# Fire_Warning.net
KiCad netlist of a schematic drawn in Altium Designer
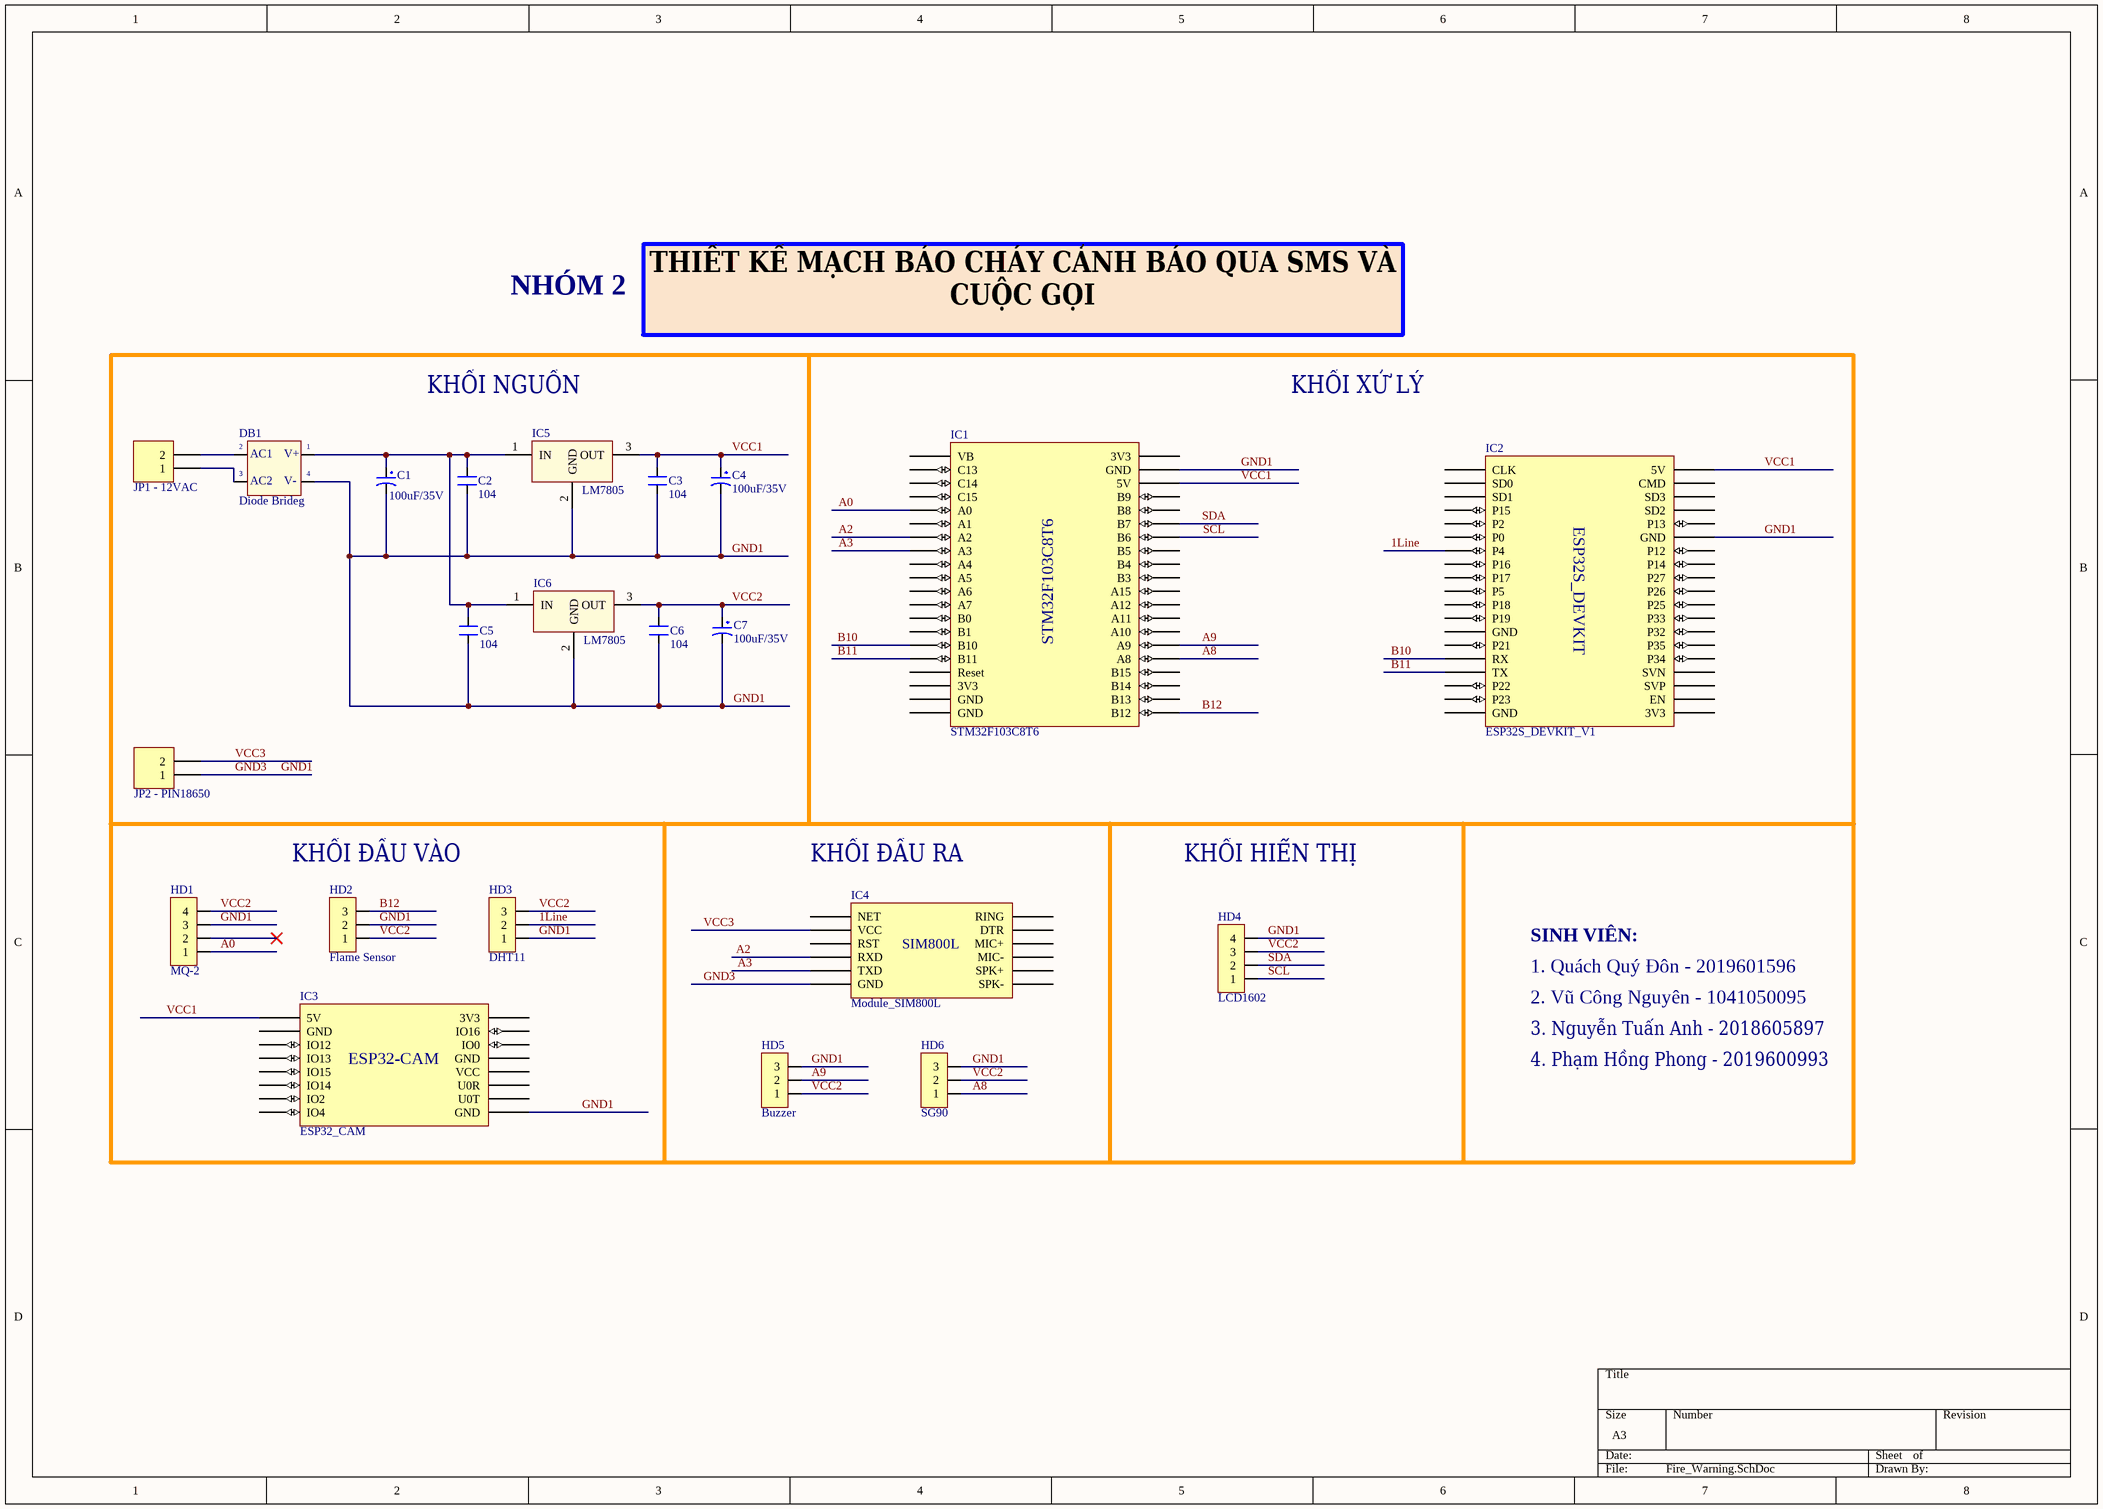
[diagram p0: Fire_Warning.SchDoc]

(export (version "E")
  (design (tool "Eeschema 10.0.6"))
  (components
    (comp (ref "C1")
      (value "100uF/35V")
      (footprint "CP1.5/3.4")
      (description "Cap 100uF/35V - 470uF/16V")
      (libsource (lib "library2") (part "CP3"))
    )
    (comp (ref "C2")
      (value "104")
      (footprint "CN2")
      (description "Cap np 104 => 105pF")
      (libsource (lib "Thuvien3D") (part "CN2"))
    )
    (comp (ref "C3")
      (value "104")
      (footprint "CN2")
      (description "Cap np 104 => 105pF")
      (libsource (lib "Thuvien3D") (part "CN2"))
    )
    (comp (ref "C4")
      (value "100uF/35V")
      (footprint "CP1.5/3.4")
      (description "Cap 100uF/35V - 470uF/16V")
      (libsource (lib "library2") (part "CP3"))
    )
    (comp (ref "C5")
      (value "104")
      (footprint "CN2")
      (description "Cap np 104 => 105pF")
      (libsource (lib "Thuvien3D") (part "CN2"))
    )
    (comp (ref "C6")
      (value "104")
      (footprint "CN2")
      (description "Cap np 104 => 105pF")
      (libsource (lib "Thuvien3D") (part "CN2"))
    )
    (comp (ref "C7")
      (value "100uF/35V")
      (footprint "CP1.5/3.4")
      (description "Cap 100uF/35V - 470uF/16V")
      (libsource (lib "library2") (part "CP3"))
    )
    (comp (ref "DB1")
      (value "Diode Brideg")
      (footprint "CAU 5A")
      (description "Convert AC to DC voltage, 4 pin")
      (libsource (lib "Thuvien3D") (part "DB"))
    )
    (comp (ref "HD1")
      (value "MQ-2")
      (footprint "HEADER 4")
      (description "Header 4P XH2.54 thẳng")
      (libsource (lib "library1") (part "Header 4_MH"))
    )
    (comp (ref "HD2")
      (value "Flame Sensor")
      (footprint "HEADER 3")
      (description "Header 3P XH2.54 thẳng")
      (libsource (lib "library1") (part "Header 3_MH"))
    )
    (comp (ref "HD3")
      (value "DHT11")
      (footprint "HEADER 3")
      (description "Header 3P XH2.54 thẳng")
      (libsource (lib "library1") (part "Header 3_MH"))
    )
    (comp (ref "HD4")
      (value "LCD1602")
      (footprint "HEADER 4")
      (description "Header 4P XH2.54 thẳng")
      (libsource (lib "library1") (part "Header 4_MH"))
    )
    (comp (ref "HD5")
      (value "Buzzer")
      (footprint "HEADER 3")
      (description "Header 3P XH2.54 thẳng")
      (libsource (lib "library1") (part "Header 3_MH"))
    )
    (comp (ref "HD6")
      (value "SG90")
      (footprint "HEADER 3")
      (description "Header 3P XH2.54 thẳng")
      (libsource (lib "library1") (part "Header 3_MH"))
    )
    (comp (ref "IC1")
      (value "STM32F103C8T6")
      (footprint "STM32F103C8T6")
      (libsource (lib "MCU") (part "STM32F103C8T6"))
    )
    (comp (ref "IC2")
      (value "ESP32S_DEVKIT_V1")
      (footprint "ESP32S_DEVKIT_V1")
      (libsource (lib "MCU") (part "ESP32S_DEVKIT_V1"))
    )
    (comp (ref "IC3") (value "ESP32_CAM") (footprint "ESP32_CAM") (libsource (lib "MCU") (part "ESP32_CAM")))
    (comp (ref "IC4")
      (value "Module_SIM800L")
      (footprint "Module Sim800L")
      (libsource (lib "MCU") (part "Module_SIM800L"))
    )
    (comp (ref "IC5")
      (value "LM7805")
      (footprint "QTO-220")
      (description "On ap +, from + 5 to + 24VDC")
      (libsource (lib "Thuvien3D") (part "LM78xx"))
    )
    (comp (ref "IC6")
      (value "LM7805")
      (footprint "QTO-220")
      (description "On ap +, from + 5 to + 24VDC")
      (libsource (lib "Thuvien3D") (part "LM78xx"))
    )
    (comp (ref "JP1 - 12VAC")
      (value "Header 2_1")
      (footprint "HED2")
      (description "Header, 2-Pin")
      (fields (field (name "MANUFACTURER") "Generic Components"))
      (libsource (lib "Thuvien3D") (part "Header 2_1"))
    )
    (comp (ref "JP2 - PIN18650")
      (value "Header 2_1")
      (footprint "HED2")
      (description "Header, 2-Pin")
      (fields (field (name "MANUFACTURER") "Generic Components"))
      (libsource (lib "Thuvien3D") (part "Header 2_1"))
    )
  )
  (nets
    (net (code "1") (name "/1Line") (class "Default")
      (node (ref "HD3") (pin "2") (pinfunction "2_2") (pintype "passive"))
      (node (ref "IC2") (pin "7") (pinfunction "P4_7") (pintype "bidirectional"))
    )
    (net (code "2") (name "/A0") (class "Default")
      (node (ref "HD1") (pin "1") (pinfunction "1_1") (pintype "passive"))
      (node (ref "IC1") (pin "24") (pinfunction "A0_24") (pintype "bidirectional"))
    )
    (net (code "3") (name "/A2") (class "Default")
      (node (ref "IC1") (pin "26") (pinfunction "A2_26") (pintype "bidirectional"))
      (node (ref "IC4") (pin "4") (pinfunction "RXD_4") (pintype "passive"))
    )
    (net (code "4") (name "/A3") (class "Default")
      (node (ref "IC1") (pin "27") (pinfunction "A3_27") (pintype "bidirectional"))
      (node (ref "IC4") (pin "5") (pinfunction "TXD_5") (pintype "passive"))
    )
    (net (code "5") (name "/A8") (class "Default")
      (node (ref "HD6") (pin "1") (pinfunction "1_1") (pintype "passive"))
      (node (ref "IC1") (pin "4") (pinfunction "A8_4") (pintype "bidirectional"))
    )
    (net (code "6") (name "/A9") (class "Default")
      (node (ref "HD5") (pin "2") (pinfunction "2_2") (pintype "passive"))
      (node (ref "IC1") (pin "5") (pinfunction "A9_5") (pintype "bidirectional"))
    )
    (net (code "7") (name "/B10") (class "Default")
      (node (ref "IC1") (pin "34") (pinfunction "B10_34") (pintype "bidirectional"))
      (node (ref "IC2") (pin "15") (pinfunction "RX_15") (pintype "passive"))
    )
    (net (code "8") (name "/B11") (class "Default")
      (node (ref "IC1") (pin "35") (pinfunction "B11_35") (pintype "bidirectional"))
      (node (ref "IC2") (pin "16") (pinfunction "TX_16") (pintype "passive"))
    )
    (net (code "9") (name "/B12") (class "Default")
      (node (ref "HD2") (pin "3") (pinfunction "3_3") (pintype "passive"))
      (node (ref "IC1") (pin "0") (pinfunction "B12_0") (pintype "bidirectional"))
    )
    (net (code "10") (name "/GND1") (class "Default")
      (node (ref "C1") (pin "2") (pinfunction "2_2") (pintype "passive"))
      (node (ref "C2") (pin "1") (pinfunction "1_1") (pintype "passive"))
      (node (ref "C3") (pin "1") (pinfunction "1_1") (pintype "passive"))
      (node (ref "C4") (pin "2") (pinfunction "2_2") (pintype "passive"))
      (node (ref "C5") (pin "1") (pinfunction "1_1") (pintype "passive"))
      (node (ref "C6") (pin "1") (pinfunction "1_1") (pintype "passive"))
      (node (ref "C7") (pin "2") (pinfunction "2_2") (pintype "passive"))
      (node (ref "DB1") (pin "4") (pinfunction "-V_OUT_4") (pintype "passive"))
      (node (ref "HD1") (pin "3") (pinfunction "3_3") (pintype "passive"))
      (node (ref "HD2") (pin "2") (pinfunction "2_2") (pintype "passive"))
      (node (ref "HD3") (pin "1") (pinfunction "1_1") (pintype "passive"))
      (node (ref "HD4") (pin "4") (pinfunction "4_4") (pintype "passive"))
      (node (ref "HD5") (pin "3") (pinfunction "3_3") (pintype "passive"))
      (node (ref "HD6") (pin "3") (pinfunction "3_3") (pintype "passive"))
      (node (ref "IC1") (pin "18") (pinfunction "GND_18") (pintype "power_in"))
      (node (ref "IC2") (pin "33") (pinfunction "GND_33") (pintype "power_in"))
      (node (ref "IC3") (pin "1") (pinfunction "GND_1") (pintype "power_in"))
      (node (ref "IC4") (pin "6") (pinfunction "GND_6") (pintype "power_in"))
      (node (ref "IC5") (pin "2") (pinfunction "GND_2") (pintype "passive"))
      (node (ref "IC6") (pin "2") (pinfunction "GND_2") (pintype "passive"))
      (node (ref "JP2 - PIN18650") (pin "1") (pinfunction "1_1") (pintype "passive"))
    )
    (net (code "11") (name "/SCL") (class "Default")
      (node (ref "HD4") (pin "1") (pinfunction "1_1") (pintype "passive"))
      (node (ref "IC1") (pin "13") (pinfunction "B6_13") (pintype "bidirectional"))
    )
    (net (code "12") (name "/SDA") (class "Default")
      (node (ref "HD4") (pin "2") (pinfunction "2_2") (pintype "passive"))
      (node (ref "IC1") (pin "14") (pinfunction "B7_14") (pintype "bidirectional"))
    )
    (net (code "13") (name "/VCC1") (class "Default")
      (node (ref "C3") (pin "2") (pinfunction "2_2") (pintype "passive"))
      (node (ref "C4") (pin "1") (pinfunction "1_1") (pintype "passive"))
      (node (ref "IC1") (pin "17") (pinfunction "5V_17") (pintype "power_in"))
      (node (ref "IC2") (pin "38") (pinfunction "5V_38") (pintype "power_in"))
      (node (ref "IC3") (pin "9") (pinfunction "5V_9") (pintype "power_in"))
      (node (ref "IC5") (pin "3") (pinfunction "OUT_3") (pintype "passive"))
    )
    (net (code "14") (name "/VCC2") (class "Default")
      (node (ref "C6") (pin "2") (pinfunction "2_2") (pintype "passive"))
      (node (ref "C7") (pin "1") (pinfunction "1_1") (pintype "passive"))
      (node (ref "HD1") (pin "4") (pinfunction "4_4") (pintype "passive"))
      (node (ref "HD2") (pin "1") (pinfunction "1_1") (pintype "passive"))
      (node (ref "HD3") (pin "3") (pinfunction "3_3") (pintype "passive"))
      (node (ref "HD4") (pin "3") (pinfunction "3_3") (pintype "passive"))
      (node (ref "HD5") (pin "1") (pinfunction "1_1") (pintype "passive"))
      (node (ref "HD6") (pin "2") (pinfunction "2_2") (pintype "passive"))
      (node (ref "IC6") (pin "3") (pinfunction "OUT_3") (pintype "passive"))
    )
    (net (code "15") (name "/VCC3") (class "Default")
      (node (ref "IC4") (pin "2") (pinfunction "VCC_2") (pintype "power_in"))
      (node (ref "JP2 - PIN18650") (pin "2") (pinfunction "2_2") (pintype "passive"))
    )
    (net (code "16") (name "Net-(DB1-+V_OUT)") (class "Default")
      (node (ref "C1") (pin "1") (pinfunction "1_1") (pintype "passive"))
      (node (ref "C2") (pin "2") (pinfunction "2_2") (pintype "passive"))
      (node (ref "C5") (pin "2") (pinfunction "2_2") (pintype "passive"))
      (node (ref "DB1") (pin "1") (pinfunction "+V_OUT_1") (pintype "passive"))
      (node (ref "IC5") (pin "1") (pinfunction "IN_1") (pintype "passive"))
      (node (ref "IC6") (pin "1") (pinfunction "IN_1") (pintype "passive"))
    )
    (net (code "17") (name "Net-(DB1-AC1)") (class "Default")
      (node (ref "DB1") (pin "2") (pinfunction "AC1_2") (pintype "passive"))
      (node (ref "JP1 - 12VAC") (pin "2") (pinfunction "2_2") (pintype "passive"))
    )
    (net (code "18") (name "Net-(DB1-AC2)") (class "Default")
      (node (ref "DB1") (pin "3") (pinfunction "AC2_3") (pintype "passive"))
      (node (ref "JP1 - 12VAC") (pin "1") (pinfunction "1_1") (pintype "passive"))
    )
    (net (code "19") (name "unconnected-(HD1-Pad2)") (class "Default")
      (node (ref "HD1") (pin "2") (pinfunction "2_2") (pintype "passive+no_connect"))
    )
    (net (code "20") (name "unconnected-(IC1-3V3-Pad19)") (class "Default")
      (node (ref "IC1") (pin "19") (pinfunction "3V3_19") (pintype "power_in"))
    )
    (net (code "21") (name "unconnected-(IC1-3V3-Pad37)") (class "Default")
      (node (ref "IC1") (pin "37") (pinfunction "3V3_37") (pintype "power_in"))
    )
    (net (code "22") (name "unconnected-(IC1-A1-Pad25)") (class "Default")
      (node (ref "IC1") (pin "25") (pinfunction "A1_25") (pintype "bidirectional"))
    )
    (net (code "23") (name "unconnected-(IC1-A4-Pad28)") (class "Default")
      (node (ref "IC1") (pin "28") (pinfunction "A4_28") (pintype "bidirectional"))
    )
    (net (code "24") (name "unconnected-(IC1-A5-Pad29)") (class "Default")
      (node (ref "IC1") (pin "29") (pinfunction "A5_29") (pintype "bidirectional"))
    )
    (net (code "25") (name "unconnected-(IC1-A6-Pad30)") (class "Default")
      (node (ref "IC1") (pin "30") (pinfunction "A6_30") (pintype "bidirectional"))
    )
    (net (code "26") (name "unconnected-(IC1-A7-Pad31)") (class "Default")
      (node (ref "IC1") (pin "31") (pinfunction "A7_31") (pintype "bidirectional"))
    )
    (net (code "27") (name "unconnected-(IC1-A10-Pad6)") (class "Default")
      (node (ref "IC1") (pin "6") (pinfunction "A10_6") (pintype "bidirectional"))
    )
    (net (code "28") (name "unconnected-(IC1-A11-Pad7)") (class "Default")
      (node (ref "IC1") (pin "7") (pinfunction "A11_7") (pintype "bidirectional"))
    )
    (net (code "29") (name "unconnected-(IC1-A12-Pad8)") (class "Default")
      (node (ref "IC1") (pin "8") (pinfunction "A12_8") (pintype "bidirectional"))
    )
    (net (code "30") (name "unconnected-(IC1-A15-Pad9)") (class "Default")
      (node (ref "IC1") (pin "9") (pinfunction "A15_9") (pintype "bidirectional"))
    )
    (net (code "31") (name "unconnected-(IC1-B0-Pad32)") (class "Default")
      (node (ref "IC1") (pin "32") (pinfunction "B0_32") (pintype "bidirectional"))
    )
    (net (code "32") (name "unconnected-(IC1-B1-Pad33)") (class "Default")
      (node (ref "IC1") (pin "33") (pinfunction "B1_33") (pintype "bidirectional"))
    )
    (net (code "33") (name "unconnected-(IC1-B3-Pad10)") (class "Default")
      (node (ref "IC1") (pin "10") (pinfunction "B3_10") (pintype "bidirectional"))
    )
    (net (code "34") (name "unconnected-(IC1-B4-Pad11)") (class "Default")
      (node (ref "IC1") (pin "11") (pinfunction "B4_11") (pintype "bidirectional"))
    )
    (net (code "35") (name "unconnected-(IC1-B5-Pad12)") (class "Default")
      (node (ref "IC1") (pin "12") (pinfunction "B5_12") (pintype "bidirectional"))
    )
    (net (code "36") (name "unconnected-(IC1-B8-Pad15)") (class "Default")
      (node (ref "IC1") (pin "15") (pinfunction "B8_15") (pintype "bidirectional"))
    )
    (net (code "37") (name "unconnected-(IC1-B9-Pad16)") (class "Default")
      (node (ref "IC1") (pin "16") (pinfunction "B9_16") (pintype "bidirectional"))
    )
    (net (code "38") (name "unconnected-(IC1-B13-Pad1)") (class "Default")
      (node (ref "IC1") (pin "1") (pinfunction "B13_1") (pintype "bidirectional"))
    )
    (net (code "39") (name "unconnected-(IC1-B14-Pad2)") (class "Default")
      (node (ref "IC1") (pin "2") (pinfunction "B14_2") (pintype "bidirectional"))
    )
    (net (code "40") (name "unconnected-(IC1-B15-Pad3)") (class "Default")
      (node (ref "IC1") (pin "3") (pinfunction "B15_3") (pintype "bidirectional"))
    )
    (net (code "41") (name "unconnected-(IC1-C13-Pad21)") (class "Default")
      (node (ref "IC1") (pin "21") (pinfunction "C13_21") (pintype "bidirectional"))
    )
    (net (code "42") (name "unconnected-(IC1-C14-Pad22)") (class "Default")
      (node (ref "IC1") (pin "22") (pinfunction "C14_22") (pintype "bidirectional"))
    )
    (net (code "43") (name "unconnected-(IC1-C15-Pad23)") (class "Default")
      (node (ref "IC1") (pin "23") (pinfunction "C15_23") (pintype "bidirectional"))
    )
    (net (code "44") (name "unconnected-(IC1-GND-Pad38)") (class "Default")
      (node (ref "IC1") (pin "38") (pinfunction "GND_38") (pintype "power_in"))
    )
    (net (code "45") (name "unconnected-(IC1-GND-Pad39)") (class "Default")
      (node (ref "IC1") (pin "39") (pinfunction "GND_39") (pintype "power_in"))
    )
    (net (code "46") (name "unconnected-(IC1-Reset-Pad36)") (class "Default")
      (node (ref "IC1") (pin "36") (pinfunction "Reset_36") (pintype "passive"))
    )
    (net (code "47") (name "unconnected-(IC1-VB-Pad20)") (class "Default")
      (node (ref "IC1") (pin "20") (pinfunction "VB_20") (pintype "passive"))
    )
    (net (code "48") (name "unconnected-(IC2-3V3-Pad20)") (class "Default")
      (node (ref "IC2") (pin "20") (pinfunction "3V3_20") (pintype "passive"))
    )
    (net (code "49") (name "unconnected-(IC2-CLK-Pad1)") (class "Default")
      (node (ref "IC2") (pin "1") (pinfunction "CLK_1") (pintype "passive"))
    )
    (net (code "50") (name "unconnected-(IC2-CMD-Pad37)") (class "Default")
      (node (ref "IC2") (pin "37") (pinfunction "CMD_37") (pintype "passive"))
    )
    (net (code "51") (name "unconnected-(IC2-EN-Pad21)") (class "Default")
      (node (ref "IC2") (pin "21") (pinfunction "EN_21") (pintype "passive"))
    )
    (net (code "52") (name "unconnected-(IC2-GND-Pad13)") (class "Default")
      (node (ref "IC2") (pin "13") (pinfunction "GND_13") (pintype "power_in"))
    )
    (net (code "53") (name "unconnected-(IC2-GND-Pad19)") (class "Default")
      (node (ref "IC2") (pin "19") (pinfunction "GND_19") (pintype "power_in"))
    )
    (net (code "54") (name "unconnected-(IC2-P0-Pad6)") (class "Default")
      (node (ref "IC2") (pin "6") (pinfunction "P0_6") (pintype "bidirectional"))
    )
    (net (code "55") (name "unconnected-(IC2-P2-Pad5)") (class "Default")
      (node (ref "IC2") (pin "5") (pinfunction "P2_5") (pintype "bidirectional"))
    )
    (net (code "56") (name "unconnected-(IC2-P5-Pad10)") (class "Default")
      (node (ref "IC2") (pin "10") (pinfunction "P5_10") (pintype "bidirectional"))
    )
    (net (code "57") (name "unconnected-(IC2-P12-Pad32)") (class "Default")
      (node (ref "IC2") (pin "32") (pinfunction "P12_32") (pintype "bidirectional"))
    )
    (net (code "58") (name "unconnected-(IC2-P13-Pad34)") (class "Default")
      (node (ref "IC2") (pin "34") (pinfunction "P13_34") (pintype "bidirectional"))
    )
    (net (code "59") (name "unconnected-(IC2-P14-Pad31)") (class "Default")
      (node (ref "IC2") (pin "31") (pinfunction "P14_31") (pintype "bidirectional"))
    )
    (net (code "60") (name "unconnected-(IC2-P15-Pad4)") (class "Default")
      (node (ref "IC2") (pin "4") (pinfunction "P15_4") (pintype "bidirectional"))
    )
    (net (code "61") (name "unconnected-(IC2-P16-Pad8)") (class "Default")
      (node (ref "IC2") (pin "8") (pinfunction "P16_8") (pintype "bidirectional"))
    )
    (net (code "62") (name "unconnected-(IC2-P17-Pad9)") (class "Default")
      (node (ref "IC2") (pin "9") (pinfunction "P17_9") (pintype "bidirectional"))
    )
    (net (code "63") (name "unconnected-(IC2-P18-Pad11)") (class "Default")
      (node (ref "IC2") (pin "11") (pinfunction "P18_11") (pintype "bidirectional"))
    )
    (net (code "64") (name "unconnected-(IC2-P19-Pad12)") (class "Default")
      (node (ref "IC2") (pin "12") (pinfunction "P19_12") (pintype "bidirectional"))
    )
    (net (code "65") (name "unconnected-(IC2-P21-Pad14)") (class "Default")
      (node (ref "IC2") (pin "14") (pinfunction "P21_14") (pintype "bidirectional"))
    )
    (net (code "66") (name "unconnected-(IC2-P22-Pad17)") (class "Default")
      (node (ref "IC2") (pin "17") (pinfunction "P22_17") (pintype "bidirectional"))
    )
    (net (code "67") (name "unconnected-(IC2-P23-Pad18)") (class "Default")
      (node (ref "IC2") (pin "18") (pinfunction "P23_18") (pintype "bidirectional"))
    )
    (net (code "68") (name "unconnected-(IC2-P25-Pad28)") (class "Default")
      (node (ref "IC2") (pin "28") (pinfunction "P25_28") (pintype "bidirectional"))
    )
    (net (code "69") (name "unconnected-(IC2-P26-Pad29)") (class "Default")
      (node (ref "IC2") (pin "29") (pinfunction "P26_29") (pintype "bidirectional"))
    )
    (net (code "70") (name "unconnected-(IC2-P27-Pad30)") (class "Default")
      (node (ref "IC2") (pin "30") (pinfunction "P27_30") (pintype "bidirectional"))
    )
    (net (code "71") (name "unconnected-(IC2-P32-Pad26)") (class "Default")
      (node (ref "IC2") (pin "26") (pinfunction "P32_26") (pintype "bidirectional"))
    )
    (net (code "72") (name "unconnected-(IC2-P33-Pad27)") (class "Default")
      (node (ref "IC2") (pin "27") (pinfunction "P33_27") (pintype "bidirectional"))
    )
    (net (code "73") (name "unconnected-(IC2-P34-Pad24)") (class "Default")
      (node (ref "IC2") (pin "24") (pinfunction "P34_24") (pintype "bidirectional"))
    )
    (net (code "74") (name "unconnected-(IC2-P35-Pad25)") (class "Default")
      (node (ref "IC2") (pin "25") (pinfunction "P35_25") (pintype "bidirectional"))
    )
    (net (code "75") (name "unconnected-(IC2-SD0-Pad2)") (class "Default")
      (node (ref "IC2") (pin "2") (pinfunction "SD0_2") (pintype "passive"))
    )
    (net (code "76") (name "unconnected-(IC2-SD1-Pad3)") (class "Default")
      (node (ref "IC2") (pin "3") (pinfunction "SD1_3") (pintype "passive"))
    )
    (net (code "77") (name "unconnected-(IC2-SD2-Pad35)") (class "Default")
      (node (ref "IC2") (pin "35") (pinfunction "SD2_35") (pintype "passive"))
    )
    (net (code "78") (name "unconnected-(IC2-SD3-Pad36)") (class "Default")
      (node (ref "IC2") (pin "36") (pinfunction "SD3_36") (pintype "passive"))
    )
    (net (code "79") (name "unconnected-(IC2-SVN-Pad23)") (class "Default")
      (node (ref "IC2") (pin "23") (pinfunction "SVN_23") (pintype "passive"))
    )
    (net (code "80") (name "unconnected-(IC2-SVP-Pad22)") (class "Default")
      (node (ref "IC2") (pin "22") (pinfunction "SVP_22") (pintype "passive"))
    )
    (net (code "81") (name "unconnected-(IC3-3V3-Pad8)") (class "Default")
      (node (ref "IC3") (pin "8") (pinfunction "3V3_8") (pintype "power_in"))
    )
    (net (code "82") (name "unconnected-(IC3-GND-Pad5)") (class "Default")
      (node (ref "IC3") (pin "5") (pinfunction "GND_5") (pintype "power_in"))
    )
    (net (code "83") (name "unconnected-(IC3-GND-Pad10)") (class "Default")
      (node (ref "IC3") (pin "10") (pinfunction "GND_10") (pintype "power_in"))
    )
    (net (code "84") (name "unconnected-(IC3-IO0-Pad6)") (class "Default")
      (node (ref "IC3") (pin "6") (pinfunction "IO0_6") (pintype "bidirectional"))
    )
    (net (code "85") (name "unconnected-(IC3-IO2-Pad15)") (class "Default")
      (node (ref "IC3") (pin "15") (pinfunction "IO2_15") (pintype "bidirectional"))
    )
    (net (code "86") (name "unconnected-(IC3-IO4-Pad16)") (class "Default")
      (node (ref "IC3") (pin "16") (pinfunction "IO4_16") (pintype "bidirectional"))
    )
    (net (code "87") (name "unconnected-(IC3-IO12-Pad11)") (class "Default")
      (node (ref "IC3") (pin "11") (pinfunction "IO12_11") (pintype "bidirectional"))
    )
    (net (code "88") (name "unconnected-(IC3-IO13-Pad12)") (class "Default")
      (node (ref "IC3") (pin "12") (pinfunction "IO13_12") (pintype "bidirectional"))
    )
    (net (code "89") (name "unconnected-(IC3-IO14-Pad14)") (class "Default")
      (node (ref "IC3") (pin "14") (pinfunction "IO14_14") (pintype "bidirectional"))
    )
    (net (code "90") (name "unconnected-(IC3-IO15-Pad13)") (class "Default")
      (node (ref "IC3") (pin "13") (pinfunction "IO15_13") (pintype "bidirectional"))
    )
    (net (code "91") (name "unconnected-(IC3-IO16-Pad7)") (class "Default")
      (node (ref "IC3") (pin "7") (pinfunction "IO16_7") (pintype "bidirectional"))
    )
    (net (code "92") (name "unconnected-(IC3-U0R-Pad3)") (class "Default")
      (node (ref "IC3") (pin "3") (pinfunction "U0R_3") (pintype "passive"))
    )
    (net (code "93") (name "unconnected-(IC3-U0T-Pad2)") (class "Default")
      (node (ref "IC3") (pin "2") (pinfunction "U0T_2") (pintype "passive"))
    )
    (net (code "94") (name "unconnected-(IC3-VCC-Pad4)") (class "Default")
      (node (ref "IC3") (pin "4") (pinfunction "VCC_4") (pintype "power_in"))
    )
    (net (code "95") (name "unconnected-(IC4-DTR-Pad11)") (class "Default")
      (node (ref "IC4") (pin "11") (pinfunction "DTR_11") (pintype "passive"))
    )
    (net (code "96") (name "unconnected-(IC4-MIC+-Pad10)") (class "Default")
      (node (ref "IC4") (pin "10") (pinfunction "MIC+_10") (pintype "passive"))
    )
    (net (code "97") (name "unconnected-(IC4-MIC--Pad9)") (class "Default")
      (node (ref "IC4") (pin "9") (pinfunction "MIC-_9") (pintype "passive"))
    )
    (net (code "98") (name "unconnected-(IC4-NET-Pad1)") (class "Default")
      (node (ref "IC4") (pin "1") (pinfunction "NET_1") (pintype "passive"))
    )
    (net (code "99") (name "unconnected-(IC4-RING-Pad12)") (class "Default")
      (node (ref "IC4") (pin "12") (pinfunction "RING_12") (pintype "passive"))
    )
    (net (code "100") (name "unconnected-(IC4-RST-Pad3)") (class "Default")
      (node (ref "IC4") (pin "3") (pinfunction "RST_3") (pintype "passive"))
    )
    (net (code "101") (name "unconnected-(IC4-SPK+-Pad8)") (class "Default")
      (node (ref "IC4") (pin "8") (pinfunction "SPK+_8") (pintype "passive"))
    )
    (net (code "102") (name "unconnected-(IC4-SPK--Pad7)") (class "Default")
      (node (ref "IC4") (pin "7") (pinfunction "SPK-_7") (pintype "passive"))
    )
  )
)
